# Dissipation_de_puissance.net
KiCad netlist of a schematic drawn in Altium Designer
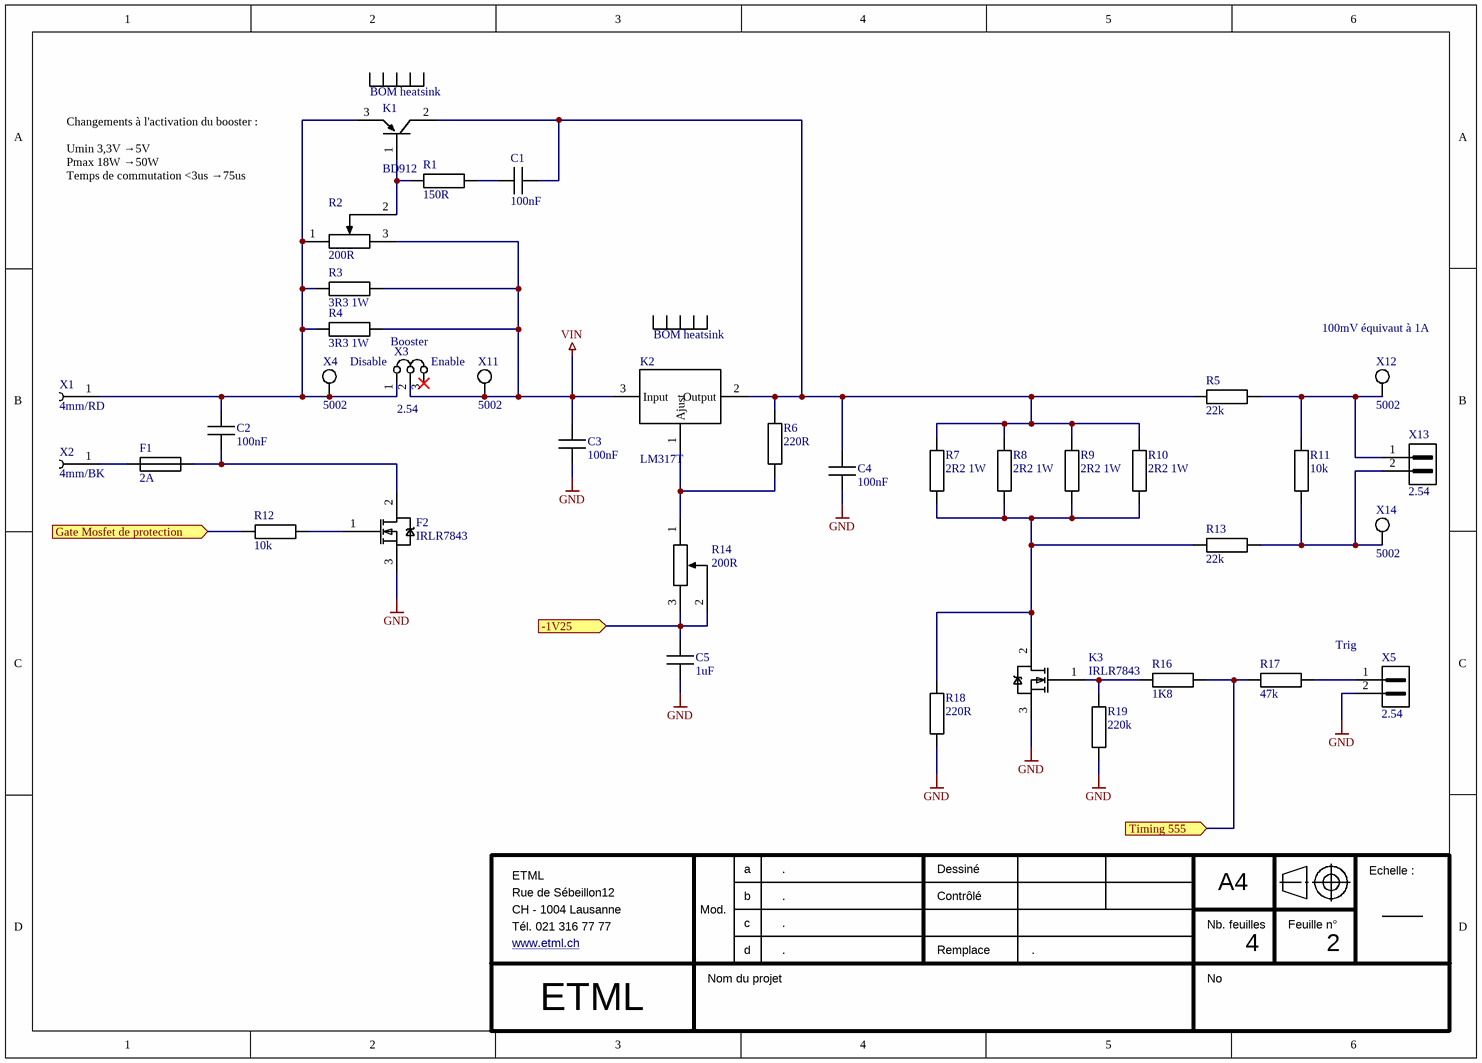
[diagram p0: Dissipation de puissance.SchDoc]

(export (version "E")
  (design (tool "Eeschema 10.0.6"))
  (components
    (comp (ref "C1")
      (value "100nF")
      (footprint "CAPC2012X08M")
      (description "CAPC 100nF X7R 50V 10% 2012 (0805 INCH)")
      (fields (field (name "VOLTAGE") "50V") (field (name "MANUFACTURER") "TDK"))
      (libsource (lib "ETML-ES") (part "CAP"))
    )
    (comp (ref "C2")
      (value "100nF")
      (footprint "CAPC2012X08M")
      (description "CAPC 100nF X7R 50V 10% 2012 (0805 INCH)")
      (fields (field (name "VOLTAGE") "50V") (field (name "MANUFACTURER") "TDK"))
      (libsource (lib "ETML-ES") (part "CAP"))
    )
    (comp (ref "C3")
      (value "100nF")
      (footprint "CAPC2012X08M")
      (description "CAPC 100nF X7R 50V 10% 2012 (0805 INCH)")
      (fields (field (name "VOLTAGE") "50V") (field (name "MANUFACTURER") "TDK"))
      (libsource (lib "ETML-ES") (part "CAP"))
    )
    (comp (ref "C4")
      (value "100nF")
      (footprint "CAPC2012X08M")
      (description "CAPC 100nF X7R 50V 10% 2012 (0805 INCH)")
      (fields (field (name "VOLTAGE") "50V") (field (name "MANUFACTURER") "TDK"))
      (libsource (lib "ETML-ES") (part "CAP"))
    )
    (comp (ref "C5")
      (value "1uF")
      (footprint "CAPC2012X08M")
      (description "CAPC 1uF X5R 25V 10% 2012 (0805 INCH)")
      (fields (field (name "MANUFACTURER") "TDK") (field (name "TOLERANCE") "±10%"))
      (libsource (lib "ETML-ES") (part "CAP"))
    )
    (comp (ref "E1")
      (value "WAKEFIELD THERMAL 678-39-C")
      (footprint "Designator")
      (description "HEAT SINK, ALUMINIUM, TO-PACKAGE, SMD")
      (libsource (lib "Custom components") (part "WAKEFIELD THERMAL 678-39-C"))
    )
    (comp (ref "E2")
      (value "WAKEFIELD THERMAL 678-39-C")
      (footprint "Designator")
      (description "HEAT SINK, ALUMINIUM, TO-PACKAGE, SMD")
      (libsource (lib "Custom components") (part "WAKEFIELD THERMAL 678-39-C"))
    )
    (comp (ref "F1")
      (value "2A")
      (footprint "WE_696103201002")
      (description "Fusible FST 2A temporisé")
      (fields (field (name "VOLTAGE") "250VAC") (field (name "MANUFACTURER") "Würth Electronik"))
      (libsource (lib "ETML-ES") (part "FUSE"))
    )
    (comp (ref "F2")
      (value "IRLR7843")
      (footprint "DPAK228P991X238-3M")
      (description "N channel Mosfet")
      (libsource (lib "Custom components") (part "IRLR7843"))
    )
    (comp (ref "K1")
      (value "BD912")
      (footprint "TO220 With WAKEFIELD THERMAL 678-39-C")
      (description "PNP transistor")
      (libsource (lib "Custom components") (part "BD912"))
    )
    (comp (ref "K2")
      (value "LM317T")
      (footprint "TO220 With WAKEFIELD THERMAL 678-39-C")
      (description "TO-220 ajustable votage regulator")
      (libsource (lib "Custom components") (part "LM317T"))
    )
    (comp (ref "K3")
      (value "IRLR7843")
      (footprint "DPAK228P991X238-3M")
      (description "N channel Mosfet")
      (libsource (lib "Custom components") (part "IRLR7843"))
    )
    (comp (ref "R1")
      (value "150R")
      (footprint "RESC2012X06M")
      (description "RES 150ohm  ±1% 0.125W 2012 (0805 INCH)")
      (fields (field (name "MANUFACTURER") "Yageo") (field (name "TOLERANCE") "±1%"))
      (libsource (lib "ETML-ES") (part "RES"))
    )
    (comp (ref "R2")
      (value "200R")
      (footprint "FP-3296W-MFG")
      (description "RESADJ 200ohm Cermet 25 turns")
      (fields (field (name "TOLERANCE") "±10%") (field (name "MANUFACTURER") "Bourns Incorporated"))
      (libsource (lib "Custom components") (part "CMP-066-000235-2"))
    )
    (comp (ref "R3")
      (value "3R3 1W")
      (footprint "NEOHM 1W ROX1S")
      (description "Résistance traversante, 3.3 ohm, ROX, 1 W, ± 5%, Axial, 350 V")
      (fields (field (name "MANUFACTURER") "Vishay") (field (name "VOLTAGE") "350V"))
      (libsource (lib "Custom components") (part "NEOHM - TE CONNECTIVITY ROX1SJ3R3"))
    )
    (comp (ref "R4")
      (value "3R3 1W")
      (footprint "NEOHM 1W ROX1S")
      (description "Résistance traversante, 3.3 ohm, ROX, 1 W, ± 5%, Axial, 350 V")
      (fields (field (name "MANUFACTURER") "Vishay") (field (name "VOLTAGE") "350V"))
      (libsource (lib "Custom components") (part "NEOHM - TE CONNECTIVITY ROX1SJ3R3"))
    )
    (comp (ref "R5")
      (value "22k")
      (footprint "RESC2012X06M")
      (description "RES 22kohm  ±1% 0.125W 2012 (0805 INCH)")
      (fields (field (name "TOLERANCE") "±1%") (field (name "MANUFACTURER") "Yageo"))
      (libsource (lib "ETML-ES") (part "RES"))
    )
    (comp (ref "R6")
      (value "220R")
      (footprint "RESC2012X06M")
      (description "RES 220ohm  ±1% 0.125W 2012 (0805 INCH)")
      (fields (field (name "MANUFACTURER") "Yageo") (field (name "VOLTAGE") "150V"))
      (libsource (lib "ETML-ES") (part "RES"))
    )
    (comp (ref "R7")
      (value "2R2 1W")
      (footprint "NEOHM 1W ROX1S")
      (description "Résistance traversante, 2.2 ohm, ROX, 1 W, ± 5%, Axial, 350 V")
      (fields (field (name "MANUFACTURER") "Vishay") (field (name "VOLTAGE") "350V"))
      (libsource (lib "Custom components") (part "NEOHM - TE CONNECTIVITY ROX1SJ2R2"))
    )
    (comp (ref "R8")
      (value "2R2 1W")
      (footprint "NEOHM 1W ROX1S")
      (description "Résistance traversante, 2.2 ohm, ROX, 1 W, ± 5%, Axial, 350 V")
      (fields (field (name "MANUFACTURER") "Vishay") (field (name "VOLTAGE") "350V"))
      (libsource (lib "Custom components") (part "NEOHM - TE CONNECTIVITY ROX1SJ2R2"))
    )
    (comp (ref "R9")
      (value "2R2 1W")
      (footprint "NEOHM 1W ROX1S")
      (description "Résistance traversante, 2.2 ohm, ROX, 1 W, ± 5%, Axial, 350 V")
      (fields (field (name "MANUFACTURER") "Vishay") (field (name "VOLTAGE") "350V"))
      (libsource (lib "Custom components") (part "NEOHM - TE CONNECTIVITY ROX1SJ2R2"))
    )
    (comp (ref "R10")
      (value "2R2 1W")
      (footprint "NEOHM 1W ROX1S")
      (description "Résistance traversante, 2.2 ohm, ROX, 1 W, ± 5%, Axial, 350 V")
      (fields (field (name "MANUFACTURER") "Vishay") (field (name "VOLTAGE") "350V"))
      (libsource (lib "Custom components") (part "NEOHM - TE CONNECTIVITY ROX1SJ2R2"))
    )
    (comp (ref "R11")
      (value "10k")
      (footprint "RESC2012X06M")
      (description "RES 10kohm  ±1% 0.125W 2012 (0805 INCH)")
      (fields (field (name "TOLERANCE") "±1%") (field (name "VOLTAGE") "150V"))
      (libsource (lib "ETML-ES") (part "RES"))
    )
    (comp (ref "R12")
      (value "10k")
      (footprint "RESC2012X06M")
      (description "RES 10kohm  ±1% 0.125W 2012 (0805 INCH)")
      (fields (field (name "TOLERANCE") "±1%") (field (name "VOLTAGE") "150V"))
      (libsource (lib "ETML-ES") (part "RES"))
    )
    (comp (ref "R13")
      (value "22k")
      (footprint "RESC2012X06M")
      (description "RES 22kohm  ±1% 0.125W 2012 (0805 INCH)")
      (fields (field (name "TOLERANCE") "±1%") (field (name "MANUFACTURER") "Yageo"))
      (libsource (lib "ETML-ES") (part "RES"))
    )
    (comp (ref "R14")
      (value "200R")
      (footprint "FP-3296W-MFG")
      (description "RESADJ 200ohm Cermet 25 turns")
      (fields (field (name "TOLERANCE") "±10%") (field (name "MANUFACTURER") "Bourns Incorporated"))
      (libsource (lib "Custom components") (part "CMP-066-000235-2"))
    )
    (comp (ref "R16")
      (value "1K8")
      (footprint "RESC2012X06M")
      (description "RES 1.8kohm  ±1% 0.125W 2012 (0805 INCH)")
      (fields (field (name "POWER") "0.125W") (field (name "VOLTAGE") "150V"))
      (libsource (lib "ETML-ES") (part "RES"))
    )
    (comp (ref "R17")
      (value "47k")
      (footprint "RESC2012X06M")
      (description "RES 47kohm  ±1% 0.125W 2012 (0805 INCH)")
      (fields (field (name "MANUFACTURER") "Yageo") (field (name "VOLTAGE") "150V"))
      (libsource (lib "ETML-ES") (part "RES"))
    )
    (comp (ref "R18")
      (value "220R")
      (footprint "RESC2012X06M")
      (description "RES 220ohm  ±1% 0.125W 2012 (0805 INCH)")
      (fields (field (name "MANUFACTURER") "Yageo") (field (name "VOLTAGE") "150V"))
      (libsource (lib "ETML-ES") (part "RES"))
    )
    (comp (ref "R19")
      (value "220k")
      (footprint "RESC2012X06M")
      (description "RES 220kohm  ±1% 0.125W 2012 (0805 INCH)")
      (fields (field (name "POWER") "0.125W") (field (name "TOLERANCE") "±1%"))
      (libsource (lib "ETML-ES") (part "RES"))
    )
    (comp (ref "X1")
      (value "4mm/RD")
      (footprint "SKS_973582101")
      (description "Embase 4mm PCB 16A 60VDC Sn Red")
      (fields (field (name "MANUFACTURER") "SKS Kontakttechnik GmbH") (field (name "VOLTAGE") "60VDC"))
      (libsource (lib "ETML-ES") (part "CON-REC-1x01"))
    )
    (comp (ref "X2")
      (value "4mm/BK")
      (footprint "SKS_973582100")
      (description "Embase 4mm PCB 16A 60VDC Sn Black")
      (fields (field (name "MANUFACTURER") "SKS Kontakttechnik GmbH") (field (name "VOLTAGE") "60VDC"))
      (libsource (lib "ETML-ES") (part "CON-REC-1x01"))
    )
    (comp (ref "X3")
      (value "2.54")
      (footprint "PIN-1x03-2.54")
      (description "JUMPER 2.54 1x03")
      (fields (field (name "MANUFACTURER") "Würth Electronik") (field (name "VOLTAGE") "250VAC"))
      (libsource (lib "ETML-ES") (part "JUMP-1x3"))
    )
    (comp (ref "X4")
      (value "5002")
      (footprint "Keystone_5002")
      (description "TEST THT MINIATURE WT")
      (fields (field (name "MANUFACTURER") "Keystone"))
      (libsource (lib "Custom components") (part "CMP-054-000004-1"))
    )
    (comp (ref "X5")
      (value "2.54")
      (footprint "PIN-1x02-2.54")
      (description "PIN HEADER 2.54 1x02")
      (fields (field (name "MANUFACTURER") "Würth Electronik") (field (name "VOLTAGE") "250V"))
      (libsource (lib "ETML-ES") (part "CON-PIN-1x02"))
    )
    (comp (ref "X11")
      (value "5002")
      (footprint "Keystone_5002")
      (description "TEST THT MINIATURE WT")
      (fields (field (name "MANUFACTURER") "Keystone"))
      (libsource (lib "Custom components") (part "CMP-054-000004-1"))
    )
    (comp (ref "X12")
      (value "5002")
      (footprint "Keystone_5002")
      (description "TEST THT MINIATURE WT")
      (fields (field (name "MANUFACTURER") "Keystone"))
      (libsource (lib "Custom components") (part "CMP-054-000004-1"))
    )
    (comp (ref "X13")
      (value "2.54")
      (footprint "PIN-1x02-2.54")
      (description "PIN HEADER 2.54 1x02")
      (fields (field (name "MANUFACTURER") "Würth Electronik") (field (name "VOLTAGE") "250V"))
      (libsource (lib "ETML-ES") (part "CON-PIN-1x02"))
    )
    (comp (ref "X14")
      (value "5002")
      (footprint "Keystone_5002")
      (description "TEST THT MINIATURE WT")
      (fields (field (name "MANUFACTURER") "Keystone"))
      (libsource (lib "Custom components") (part "CMP-054-000004-1"))
    )
  )
  (nets
    (net (code "1") (name "/-1V25") (class "Default")
      (node (ref "C5") (pin "2") (pinfunction "2_2") (pintype "passive"))
      (node (ref "R14") (pin "2") (pinfunction "2_2") (pintype "passive"))
      (node (ref "R14") (pin "3") (pinfunction "3_3") (pintype "passive"))
    )
    (net (code "2") (name "/Gate Mosfet de protection") (class "Default")
      (node (ref "R12") (pin "1") (pinfunction "1_1") (pintype "passive"))
    )
    (net (code "3") (name "/Timing 555") (class "Default")
      (node (ref "R16") (pin "2") (pinfunction "2_2") (pintype "passive"))
      (node (ref "R17") (pin "1") (pinfunction "1_1") (pintype "passive"))
    )
    (net (code "4") (name "GND") (class "Default")
      (node (ref "C3") (pin "1") (pinfunction "1_1") (pintype "passive"))
      (node (ref "C4") (pin "1") (pinfunction "1_1") (pintype "passive"))
      (node (ref "C5") (pin "1") (pinfunction "1_1") (pintype "passive"))
      (node (ref "F2") (pin "3") (pinfunction "S_3") (pintype "passive"))
      (node (ref "K3") (pin "3") (pinfunction "S_3") (pintype "passive"))
      (node (ref "R18") (pin "1") (pinfunction "1_1") (pintype "passive"))
      (node (ref "R19") (pin "1") (pinfunction "1_1") (pintype "passive"))
      (node (ref "X5") (pin "2") (pinfunction "2_2") (pintype "passive"))
    )
    (net (code "5") (name "Net-(C1-Pad2)") (class "Default")
      (node (ref "C1") (pin "2") (pinfunction "2_2") (pintype "passive"))
      (node (ref "R1") (pin "2") (pinfunction "2_2") (pintype "passive"))
    )
    (net (code "6") (name "Net-(F1-Pad1)") (class "Default")
      (node (ref "F1") (pin "1") (pinfunction "1_1") (pintype "passive"))
      (node (ref "X2") (pin "1") (pinfunction "1_1") (pintype "passive"))
    )
    (net (code "7") (name "Net-(F2-D)") (class "Default")
      (node (ref "C2") (pin "1") (pinfunction "1_1") (pintype "passive"))
      (node (ref "F1") (pin "2") (pinfunction "2_2") (pintype "passive"))
      (node (ref "F2") (pin "2") (pinfunction "D_2") (pintype "passive"))
    )
    (net (code "8") (name "Net-(F2-G)") (class "Default")
      (node (ref "F2") (pin "1") (pinfunction "G_1") (pintype "passive"))
      (node (ref "R12") (pin "2") (pinfunction "2_2") (pintype "passive"))
    )
    (net (code "9") (name "Net-(K1-Base)") (class "Default")
      (node (ref "K1") (pin "1") (pinfunction "Base_1") (pintype "passive"))
      (node (ref "R1") (pin "1") (pinfunction "1_1") (pintype "passive"))
      (node (ref "R2") (pin "2") (pinfunction "2_2") (pintype "passive"))
    )
    (net (code "10") (name "Net-(K1-Collector)") (class "Default")
      (node (ref "C1") (pin "1") (pinfunction "1_1") (pintype "passive"))
      (node (ref "C4") (pin "2") (pinfunction "2_2") (pintype "passive"))
      (node (ref "K1") (pin "2") (pinfunction "Collector_2") (pintype "passive"))
      (node (ref "K2") (pin "2") (pinfunction "Output_2") (pintype "passive"))
      (node (ref "R10") (pin "2") (pinfunction "2_2") (pintype "passive"))
      (node (ref "R5") (pin "1") (pinfunction "1_1") (pintype "passive"))
      (node (ref "R6") (pin "2") (pinfunction "2_2") (pintype "passive"))
      (node (ref "R7") (pin "2") (pinfunction "2_2") (pintype "passive"))
      (node (ref "R8") (pin "2") (pinfunction "2_2") (pintype "passive"))
      (node (ref "R9") (pin "2") (pinfunction "2_2") (pintype "passive"))
    )
    (net (code "11") (name "Net-(K1-Emitter)") (class "Default")
      (node (ref "C2") (pin "2") (pinfunction "2_2") (pintype "passive"))
      (node (ref "K1") (pin "3") (pinfunction "Emitter_3") (pintype "passive"))
      (node (ref "R2") (pin "1") (pinfunction "1_1") (pintype "passive"))
      (node (ref "R3") (pin "1") (pinfunction "1_1") (pintype "passive"))
      (node (ref "R4") (pin "1") (pinfunction "1_1") (pintype "passive"))
      (node (ref "X1") (pin "1") (pinfunction "1_1") (pintype "passive"))
      (node (ref "X3") (pin "1") (pinfunction "0_1") (pintype "passive"))
      (node (ref "X4") (pin "1") (pinfunction "TP_1") (pintype "passive"))
    )
    (net (code "12") (name "Net-(K2-Ajust)") (class "Default")
      (node (ref "K2") (pin "1") (pinfunction "Ajust_1") (pintype "passive"))
      (node (ref "R14") (pin "1") (pinfunction "1_1") (pintype "passive"))
      (node (ref "R6") (pin "1") (pinfunction "1_1") (pintype "passive"))
    )
    (net (code "13") (name "Net-(K3-D)") (class "Default")
      (node (ref "K3") (pin "2") (pinfunction "D_2") (pintype "passive"))
      (node (ref "R10") (pin "1") (pinfunction "1_1") (pintype "passive"))
      (node (ref "R13") (pin "1") (pinfunction "1_1") (pintype "passive"))
      (node (ref "R18") (pin "2") (pinfunction "2_2") (pintype "passive"))
      (node (ref "R7") (pin "1") (pinfunction "1_1") (pintype "passive"))
      (node (ref "R8") (pin "1") (pinfunction "1_1") (pintype "passive"))
      (node (ref "R9") (pin "1") (pinfunction "1_1") (pintype "passive"))
    )
    (net (code "14") (name "Net-(K3-G)") (class "Default")
      (node (ref "K3") (pin "1") (pinfunction "G_1") (pintype "passive"))
      (node (ref "R16") (pin "1") (pinfunction "1_1") (pintype "passive"))
      (node (ref "R19") (pin "2") (pinfunction "2_2") (pintype "passive"))
    )
    (net (code "15") (name "Net-(R17-Pad2)") (class "Default")
      (node (ref "R17") (pin "2") (pinfunction "2_2") (pintype "passive"))
      (node (ref "X5") (pin "1") (pinfunction "1_1") (pintype "passive"))
    )
    (net (code "16") (name "Net-(X12-TP)") (class "Default")
      (node (ref "R11") (pin "2") (pinfunction "2_2") (pintype "passive"))
      (node (ref "R5") (pin "2") (pinfunction "2_2") (pintype "passive"))
      (node (ref "X12") (pin "1") (pinfunction "TP_1") (pintype "passive"))
      (node (ref "X13") (pin "1") (pinfunction "1_1") (pintype "passive"))
    )
    (net (code "17") (name "Net-(X14-TP)") (class "Default")
      (node (ref "R11") (pin "1") (pinfunction "1_1") (pintype "passive"))
      (node (ref "R13") (pin "2") (pinfunction "2_2") (pintype "passive"))
      (node (ref "X13") (pin "2") (pinfunction "2_2") (pintype "passive"))
      (node (ref "X14") (pin "1") (pinfunction "TP_1") (pintype "passive"))
    )
    (net (code "18") (name "VIN") (class "Default")
      (node (ref "C3") (pin "2") (pinfunction "2_2") (pintype "passive"))
      (node (ref "K2") (pin "3") (pinfunction "Input_3") (pintype "passive"))
      (node (ref "R2") (pin "3") (pinfunction "3_3") (pintype "passive"))
      (node (ref "R3") (pin "2") (pinfunction "2_2") (pintype "passive"))
      (node (ref "R4") (pin "2") (pinfunction "2_2") (pintype "passive"))
      (node (ref "X11") (pin "1") (pinfunction "TP_1") (pintype "passive"))
      (node (ref "X3") (pin "2") (pinfunction "2_2") (pintype "passive"))
    )
    (net (code "19") (name "unconnected-(X3-Pad3)") (class "Default")
      (node (ref "X3") (pin "3") (pinfunction "3_3") (pintype "passive+no_connect"))
    )
  )
)
